# NOR_gate.net
KiCad netlist of a schematic drawn in EAGLE
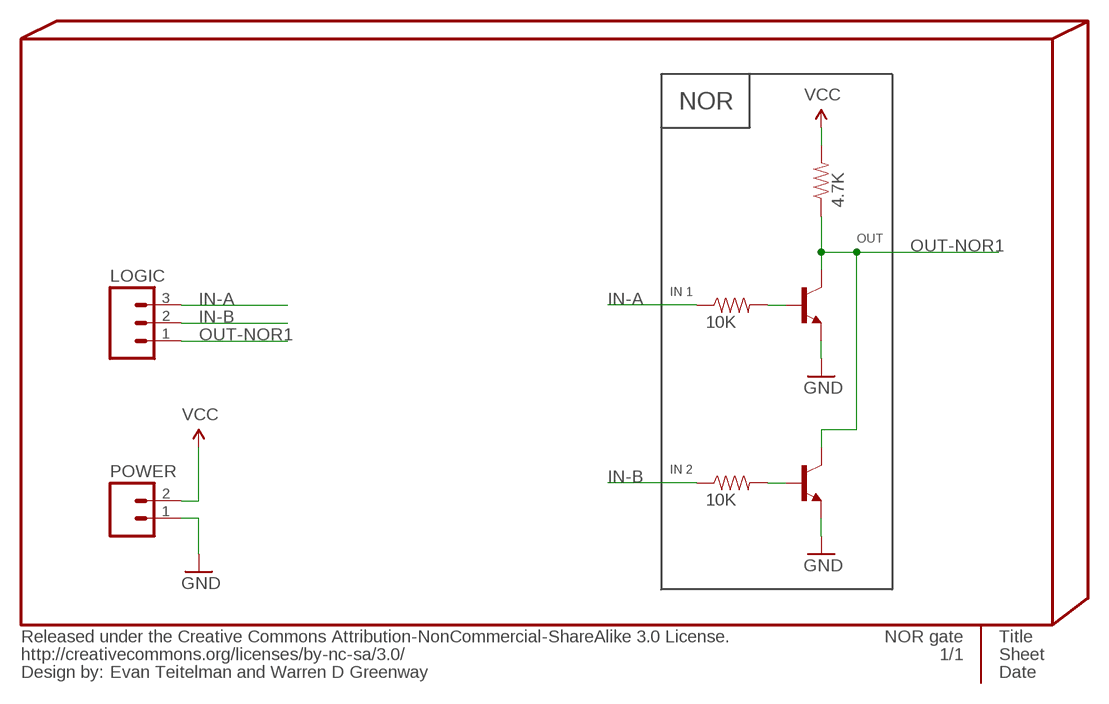
[diagram p0: schematic, sheet 1]

(export (version "E")
  (design (tool "Eeschema 10.0.6"))
  (components
    (comp (ref "INFO4")
      (value "Evan Teitelman and Warren D Greenway")
      (footprint "eagle-import:%CC-NC-SA")
      (libsource (lib "eagle-import") (part "%CC-NC-SA"))
    )
    (comp (ref "LOGIC")
      (value "M03PTH")
      (footprint "eagle-import:1X03")
      (libsource (lib "eagle-import") (part "M03PTH"))
    )
    (comp (ref "POWER")
      (value "M02PTH")
      (footprint "eagle-import:1X02")
      (libsource (lib "eagle-import") (part "M02PTH"))
    )
    (comp (ref "PUR-NOR1")
      (value "4.7K")
      (footprint "eagle-import:0402-RES")
      (libsource (lib "eagle-import") (part "RESISTOR0402-RES"))
    )
    (comp (ref "Q1-NOR1")
      (value "TRANSISTOR_NPNSOT23")
      (footprint "eagle-import:SOT23")
      (libsource (lib "eagle-import") (part "TRANSISTOR_NPNSOT23"))
    )
    (comp (ref "Q2-NOR1")
      (value "TRANSISTOR_NPNSOT23")
      (footprint "eagle-import:SOT23")
      (libsource (lib "eagle-import") (part "TRANSISTOR_NPNSOT23"))
    )
    (comp (ref "R1-NOR1")
      (value "10K")
      (footprint "eagle-import:0402-RES")
      (libsource (lib "eagle-import") (part "RESISTOR0402-RES"))
    )
    (comp (ref "R2-NOR1")
      (value "10K")
      (footprint "eagle-import:0402-RES")
      (libsource (lib "eagle-import") (part "RESISTOR0402-RES"))
    )
  )
  (nets
    (net (code "1") (name "/IN-A") (class "Default")
      (node (ref "LOGIC") (pin "3") (pinfunction "3_3") (pintype "passive"))
      (node (ref "R1-NOR1") (pin "1") (pinfunction "1_1") (pintype "passive"))
    )
    (net (code "2") (name "/IN-B") (class "Default")
      (node (ref "LOGIC") (pin "2") (pinfunction "2_2") (pintype "passive"))
      (node (ref "R2-NOR1") (pin "1") (pinfunction "1_1") (pintype "passive"))
    )
    (net (code "3") (name "/OUT-NOR1") (class "Default")
      (node (ref "LOGIC") (pin "1") (pinfunction "1_1") (pintype "passive"))
      (node (ref "PUR-NOR1") (pin "1") (pinfunction "1_1") (pintype "passive"))
      (node (ref "Q1-NOR1") (pin "3") (pinfunction "C_3") (pintype "passive"))
      (node (ref "Q2-NOR1") (pin "3") (pinfunction "C_3") (pintype "passive"))
    )
    (net (code "4") (name "@GND") (class "Default")
      (node (ref "POWER") (pin "1") (pinfunction "1_1") (pintype "passive"))
      (node (ref "Q1-NOR1") (pin "2") (pinfunction "E_2") (pintype "passive"))
      (node (ref "Q2-NOR1") (pin "2") (pinfunction "E_2") (pintype "passive"))
    )
    (net (code "5") (name "@VCC") (class "Default")
      (node (ref "POWER") (pin "2") (pinfunction "2_2") (pintype "passive"))
      (node (ref "PUR-NOR1") (pin "2") (pinfunction "2_2") (pintype "passive"))
    )
    (net (code "6") (name "Net-(Q1-NOR1-B)") (class "Default")
      (node (ref "Q1-NOR1") (pin "1") (pinfunction "B_1") (pintype "passive"))
      (node (ref "R1-NOR1") (pin "2") (pinfunction "2_2") (pintype "passive"))
    )
    (net (code "7") (name "Net-(Q2-NOR1-B)") (class "Default")
      (node (ref "Q2-NOR1") (pin "1") (pinfunction "B_1") (pintype "passive"))
      (node (ref "R2-NOR1") (pin "2") (pinfunction "2_2") (pintype "passive"))
    )
  )
)
